# HGD_Sensor_v0_2_-20200901.net
KiCad netlist of a schematic drawn in Altium Designer
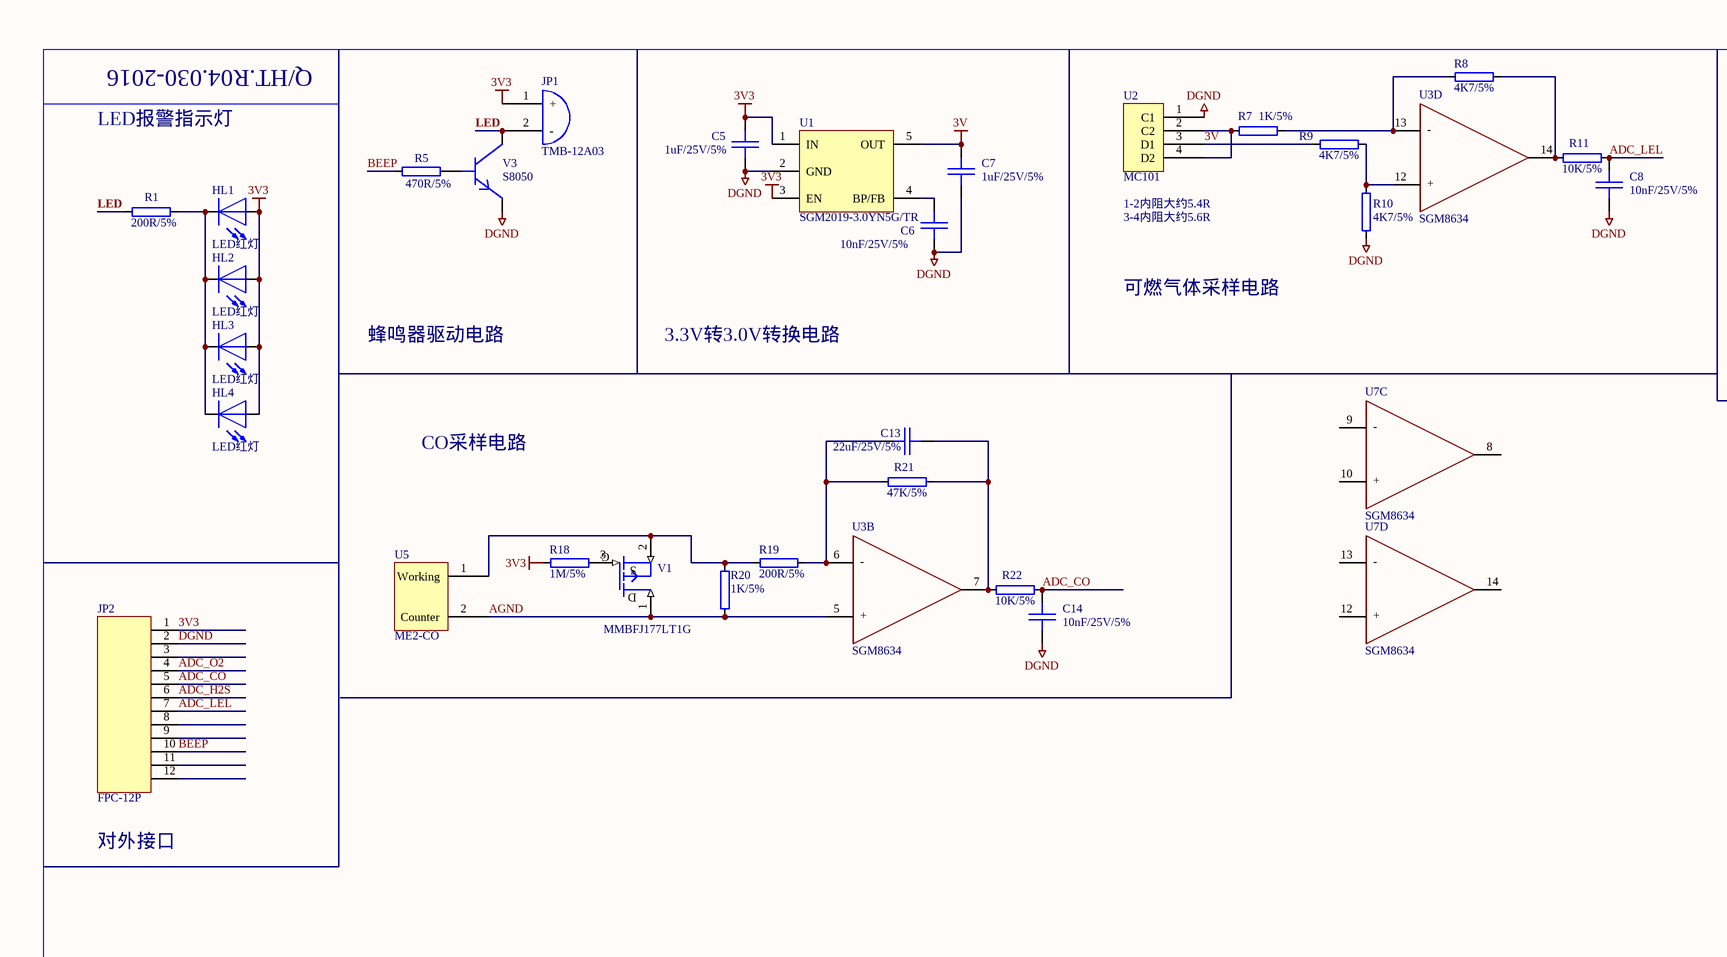
[diagram p0: HGD_Sensor(v0.2)-20200901.SchDoc, top left]
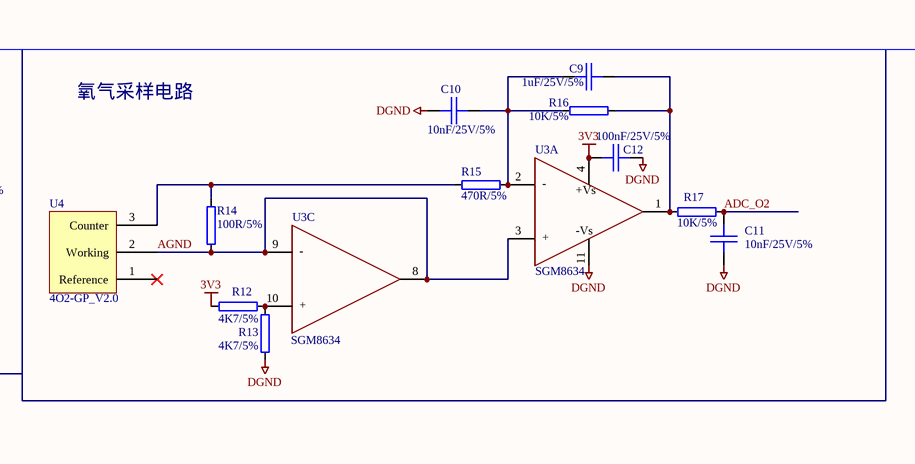
[diagram p1: HGD_Sensor(v0.2)-20200901.SchDoc, top right]
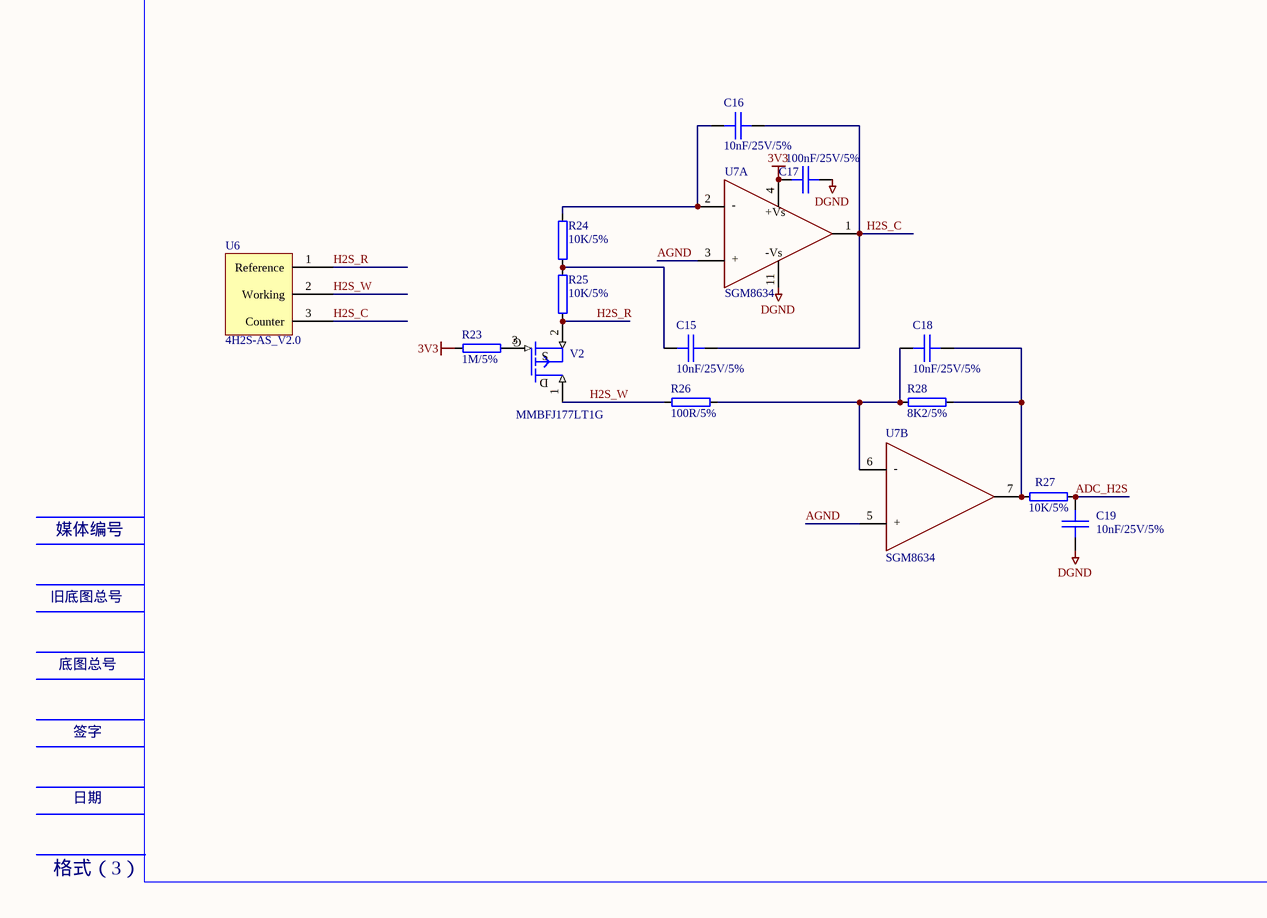
[diagram p2: HGD_Sensor(v0.2)-20200901.SchDoc, bottom left]
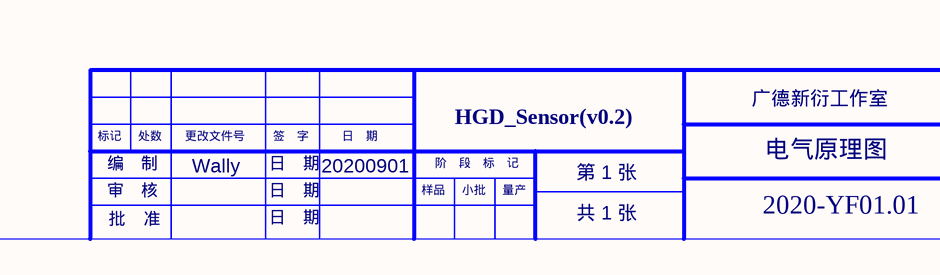
[diagram p3: HGD_Sensor(v0.2)-20200901.SchDoc, bottom right]

(export (version "E")
  (design (tool "Eeschema 10.0.6"))
  (components
    (comp (ref "C5")
      (value "1uF/25V/5%")
      (footprint "0805")
      (description "电容")
      (libsource (lib "*") (part "CAP"))
    )
    (comp (ref "C6")
      (value "10nF/25V/5%")
      (footprint "C0603")
      (description "电容")
      (libsource (lib "*") (part "CAP"))
    )
    (comp (ref "C7")
      (value "1uF/25V/5%")
      (footprint "0805")
      (description "电容")
      (libsource (lib "*") (part "CAP"))
    )
    (comp (ref "C8")
      (value "10nF/25V/5%")
      (footprint "C0603")
      (description "电容")
      (libsource (lib "*") (part "CAP"))
    )
    (comp (ref "C9")
      (value "1uF/25V/5%")
      (footprint "0805")
      (description "电容")
      (libsource (lib "*") (part "CAP"))
    )
    (comp (ref "C10")
      (value "10nF/25V/5%")
      (footprint "C0603")
      (description "电容")
      (libsource (lib "*") (part "CAP"))
    )
    (comp (ref "C11")
      (value "10nF/25V/5%")
      (footprint "C0603")
      (description "电容")
      (libsource (lib "*") (part "CAP"))
    )
    (comp (ref "C12")
      (value "100nF/25V/5%")
      (footprint "C0603")
      (description "电容")
      (libsource (lib "*") (part "CAP"))
    )
    (comp (ref "C13")
      (value "22uF/25V/5%")
      (footprint "0805")
      (description "电容")
      (libsource (lib "*") (part "CAP"))
    )
    (comp (ref "C14")
      (value "10nF/25V/5%")
      (footprint "C0603")
      (description "电容")
      (libsource (lib "*") (part "CAP"))
    )
    (comp (ref "C15")
      (value "10nF/25V/5%")
      (footprint "C0603")
      (description "电容")
      (libsource (lib "*") (part "CAP"))
    )
    (comp (ref "C16")
      (value "10nF/25V/5%")
      (footprint "C0603")
      (description "电容")
      (libsource (lib "*") (part "CAP"))
    )
    (comp (ref "C17")
      (value "100nF/25V/5%")
      (footprint "C0603")
      (description "电容")
      (libsource (lib "*") (part "CAP"))
    )
    (comp (ref "C18")
      (value "10nF/25V/5%")
      (footprint "C0603")
      (description "电容")
      (libsource (lib "*") (part "CAP"))
    )
    (comp (ref "C19")
      (value "10nF/25V/5%")
      (footprint "C0603")
      (description "电容")
      (libsource (lib "*") (part "CAP"))
    )
    (comp (ref "HL1")
      (value "LED红灯")
      (footprint "LED-3MM")
      (description "发光二极管")
      (libsource (lib "wypPCB_Lib") (part "发光二极管"))
    )
    (comp (ref "HL2")
      (value "LED红灯")
      (footprint "LED-3MM")
      (description "发光二极管")
      (libsource (lib "wypPCB_Lib") (part "发光二极管"))
    )
    (comp (ref "HL3")
      (value "LED红灯")
      (footprint "LED-3MM")
      (description "发光二极管")
      (libsource (lib "wypPCB_Lib") (part "发光二极管"))
    )
    (comp (ref "HL4")
      (value "LED红灯")
      (footprint "LED-3MM")
      (description "发光二极管")
      (libsource (lib "wypPCB_Lib") (part "发光二极管"))
    )
    (comp (ref "JP1")
      (value "TMB-12A03")
      (footprint "TMB-12A03")
      (description "TMB-12A03：3.3V有源蜂鸣器")
      (libsource (lib "wypPCB_Lib") (part "TMB-12A03"))
    )
    (comp (ref "JP2")
      (value "FPC-12P")
      (footprint "FPC-1.0MM-12P-W")
      (libsource (lib "wypPCB_Lib") (part "FPC-12P"))
    )
    (comp (ref "R1")
      (value "200R/5%")
      (footprint "R0603")
      (description "电阻")
      (libsource (lib "*") (part "RES2"))
    )
    (comp (ref "R5")
      (value "470R/5%")
      (footprint "R0603")
      (description "电阻")
      (libsource (lib "*") (part "RES2"))
    )
    (comp (ref "R7")
      (value "1K/5%")
      (footprint "R0603")
      (description "电阻")
      (libsource (lib "*") (part "RES2"))
    )
    (comp (ref "R8")
      (value "4K7/5%")
      (footprint "R0603")
      (description "电阻")
      (libsource (lib "*") (part "RES2"))
    )
    (comp (ref "R9")
      (value "4K7/5%")
      (footprint "R0603")
      (description "电阻")
      (libsource (lib "*") (part "RES2"))
    )
    (comp (ref "R10")
      (value "4K7/5%")
      (footprint "R0603")
      (description "电阻")
      (libsource (lib "*") (part "RES2"))
    )
    (comp (ref "R11")
      (value "10K/5%")
      (footprint "R0603")
      (description "电阻")
      (libsource (lib "*") (part "RES2"))
    )
    (comp (ref "R12")
      (value "4K7/5%")
      (footprint "R0603")
      (description "电阻")
      (libsource (lib "*") (part "RES2"))
    )
    (comp (ref "R13")
      (value "4K7/5%")
      (footprint "R0603")
      (description "电阻")
      (libsource (lib "*") (part "RES2"))
    )
    (comp (ref "R14")
      (value "100R/5%")
      (footprint "R0603")
      (description "电阻")
      (libsource (lib "*") (part "RES2"))
    )
    (comp (ref "R15")
      (value "470R/5%")
      (footprint "R0603")
      (description "电阻")
      (libsource (lib "*") (part "RES2"))
    )
    (comp (ref "R16")
      (value "10K/5%")
      (footprint "R0603")
      (description "电阻")
      (libsource (lib "*") (part "RES2"))
    )
    (comp (ref "R17")
      (value "10K/5%")
      (footprint "R0603")
      (description "电阻")
      (libsource (lib "*") (part "RES2"))
    )
    (comp (ref "R18")
      (value "1M/5%")
      (footprint "R0603")
      (description "电阻")
      (libsource (lib "*") (part "RES2"))
    )
    (comp (ref "R19")
      (value "200R/5%")
      (footprint "R0603")
      (description "电阻")
      (libsource (lib "*") (part "RES2"))
    )
    (comp (ref "R20")
      (value "1K/5%")
      (footprint "R0603")
      (description "电阻")
      (libsource (lib "*") (part "RES2"))
    )
    (comp (ref "R21")
      (value "47K/5%")
      (footprint "R0603")
      (description "电阻")
      (libsource (lib "*") (part "RES2"))
    )
    (comp (ref "R22")
      (value "10K/5%")
      (footprint "R0603")
      (description "电阻")
      (libsource (lib "*") (part "RES2"))
    )
    (comp (ref "R23")
      (value "1M/5%")
      (footprint "R0603")
      (description "电阻")
      (libsource (lib "*") (part "RES2"))
    )
    (comp (ref "R24")
      (value "10K/5%")
      (footprint "R0603")
      (description "电阻")
      (libsource (lib "*") (part "RES2"))
    )
    (comp (ref "R25")
      (value "10K/5%")
      (footprint "R0603")
      (description "电阻")
      (libsource (lib "*") (part "RES2"))
    )
    (comp (ref "R26")
      (value "100R/5%")
      (footprint "R0603")
      (description "电阻")
      (libsource (lib "*") (part "RES2"))
    )
    (comp (ref "R27")
      (value "10K/5%")
      (footprint "R0603")
      (description "电阻")
      (libsource (lib "*") (part "RES2"))
    )
    (comp (ref "R28")
      (value "8K2/5%")
      (footprint "R0603")
      (description "电阻")
      (libsource (lib "*") (part "RES2"))
    )
    (comp (ref "U1")
      (value "SGM2019-3.0YN5G/TR")
      (footprint "SGM2019_SOT23-5_95P280X125-5N")
      (description "SGM2019：Low Power, Low Dropout, RF Linear Regulators")
      (libsource (lib "wypPCB_Lib") (part "SGM2019"))
    )
    (comp (ref "U2")
      (value "MC101")
      (footprint "MC101")
      (description "MC101：可燃气体传感器")
      (libsource (lib "wypPCB_Lib") (part "MC101"))
    )
    (comp (ref "U3")
      (value "SGM8634")
      (footprint "SGM8634_TSSOP14_65P640X120-14N")
      (description "SGM8634：470μA, 6MHz, Rail-to-Rail I/O, CMOS Operational Amplifier")
      (libsource (lib "wypPCB_Lib") (part "SGM8634"))
    )
    (comp (ref "U4")
      (value "4O2-GP_V2.0")
      (footprint "4O2-GP_V2.0-1.5K-3.2*2.5*5.8")
      (description "4O2-GP_V2.0：O2传感器")
      (libsource (lib "wypPCB_Lib") (part "4O2-GP_V2.0"))
    )
    (comp (ref "U5")
      (value "ME2-CO")
      (footprint "ME2-CO_1.5K-3.2*2.5*5.8")
      (description "ME2-CO：CO传感器")
      (libsource (lib "wypPCB_Lib") (part "ME2-CO"))
    )
    (comp (ref "U6")
      (value "4H2S-AS_V2.0")
      (footprint "4H2S-AS_V2.0-1.5K-3.0*2.5*5.8")
      (description "4H2S-AS_V2.0：H2S传感器")
      (libsource (lib "wypPCB_Lib") (part "4H2S-AS_V2.0"))
    )
    (comp (ref "U7")
      (value "SGM8634")
      (footprint "SGM8634_TSSOP14_65P640X120-14N")
      (description "SGM8634：470μA, 6MHz, Rail-to-Rail I/O, CMOS Operational Amplifier")
      (libsource (lib "wypPCB_Lib") (part "SGM8634"))
    )
    (comp (ref "V1")
      (value "MMBFJ177LT1G")
      (footprint "MMBFJ177LT1G_SOT-23")
      (description "MMBFJ177LT1G：P-JFET?Chopper")
      (libsource (lib "wypPCB_Lib") (part "MMBFJ177LT1G"))
    )
    (comp (ref "V2")
      (value "MMBFJ177LT1G")
      (footprint "MMBFJ177LT1G_SOT-23")
      (description "MMBFJ177LT1G：P-JFET?Chopper")
      (libsource (lib "wypPCB_Lib") (part "MMBFJ177LT1G"))
    )
    (comp (ref "V3")
      (value "S8050")
      (footprint "SOT-23")
      (description "NPN三极管")
      (libsource (lib "ESLIB(v1.1)-AD9-20150731") (part "NPN"))
    )
  )
  (nets
    (net (code "1") (name "/ADC_CO") (class "Default")
      (node (ref "C14") (pin "1") (pintype "passive"))
      (node (ref "JP2") (pin "5") (pintype "passive"))
      (node (ref "R22") (pin "1") (pintype "passive"))
    )
    (net (code "2") (name "/ADC_H2S") (class "Default")
      (node (ref "C19") (pin "1") (pintype "passive"))
      (node (ref "JP2") (pin "6") (pintype "passive"))
      (node (ref "R27") (pin "2") (pintype "passive"))
    )
    (net (code "3") (name "/ADC_LEL") (class "Default")
      (node (ref "C8") (pin "1") (pintype "passive"))
      (node (ref "JP2") (pin "7") (pintype "passive"))
      (node (ref "R11") (pin "1") (pintype "passive"))
    )
    (net (code "4") (name "/ADC_O2") (class "Default")
      (node (ref "C11") (pin "1") (pintype "passive"))
      (node (ref "JP2") (pin "4") (pintype "passive"))
      (node (ref "R17") (pin "1") (pintype "passive"))
    )
    (net (code "5") (name "/AGND") (class "Default")
      (node (ref "R14") (pin "1") (pintype "passive"))
      (node (ref "R20") (pin "2") (pintype "passive"))
      (node (ref "U3") (pin "3") (pinfunction "+_3") (pintype "passive"))
      (node (ref "U3") (pin "5") (pinfunction "+_5") (pintype "passive"))
      (node (ref "U3") (pin "8") (pintype "passive"))
      (node (ref "U3") (pin "9") (pinfunction "-_9") (pintype "passive"))
      (node (ref "U4") (pin "2") (pinfunction "Working_2") (pintype "passive"))
      (node (ref "U5") (pin "2") (pinfunction "Counter_2") (pintype "passive"))
      (node (ref "U7") (pin "3") (pinfunction "+_3") (pintype "passive"))
      (node (ref "U7") (pin "5") (pinfunction "+_5") (pintype "passive"))
      (node (ref "V1") (pin "1") (pinfunction "D_1") (pintype "input"))
    )
    (net (code "6") (name "/BEEP") (class "Default")
      (node (ref "JP2") (pin "10") (pintype "passive"))
      (node (ref "R5") (pin "1") (pintype "passive"))
    )
    (net (code "7") (name "/H2S_C") (class "Default")
      (node (ref "C15") (pin "1") (pintype "passive"))
      (node (ref "C16") (pin "2") (pintype "passive"))
      (node (ref "U6") (pin "3") (pinfunction "Counter_3") (pintype "passive"))
      (node (ref "U7") (pin "1") (pintype "passive"))
    )
    (net (code "8") (name "/H2S_R") (class "Default")
      (node (ref "R25") (pin "2") (pintype "passive"))
      (node (ref "U6") (pin "1") (pinfunction "Reference_1") (pintype "passive"))
      (node (ref "V2") (pin "2") (pinfunction "S_2") (pintype "input"))
    )
    (net (code "9") (name "/H2S_W") (class "Default")
      (node (ref "R26") (pin "1") (pintype "passive"))
      (node (ref "U6") (pin "2") (pinfunction "Working_2") (pintype "passive"))
      (node (ref "V2") (pin "1") (pinfunction "D_1") (pintype "input"))
    )
    (net (code "10") (name "/LED") (class "Default")
      (node (ref "JP1") (pin "2") (pinfunction "-_2") (pintype "passive"))
      (node (ref "R1") (pin "2") (pintype "passive"))
      (node (ref "V3") (pin "C") (pintype "passive"))
    )
    (net (code "11") (name "3V") (class "Default")
      (node (ref "C7") (pin "1") (pintype "passive"))
      (node (ref "R9") (pin "2") (pintype "passive"))
      (node (ref "U1") (pin "5") (pinfunction "OUT_5") (pintype "passive"))
      (node (ref "U2") (pin "3") (pinfunction "D1_3") (pintype "passive"))
    )
    (net (code "12") (name "3V3") (class "Default")
      (node (ref "C12") (pin "2") (pintype "passive"))
      (node (ref "C17") (pin "2") (pintype "passive"))
      (node (ref "C5") (pin "1") (pintype "passive"))
      (node (ref "HL1") (pin "A") (pintype "passive"))
      (node (ref "HL2") (pin "A") (pintype "passive"))
      (node (ref "HL3") (pin "A") (pintype "passive"))
      (node (ref "HL4") (pin "A") (pintype "passive"))
      (node (ref "JP1") (pin "1") (pinfunction "+_1") (pintype "passive"))
      (node (ref "JP2") (pin "1") (pintype "passive"))
      (node (ref "R12") (pin "2") (pintype "passive"))
      (node (ref "R18") (pin "2") (pintype "passive"))
      (node (ref "R23") (pin "2") (pintype "passive"))
      (node (ref "U1") (pin "1") (pinfunction "IN_1") (pintype "passive"))
      (node (ref "U1") (pin "3") (pinfunction "EN_3") (pintype "passive"))
      (node (ref "U3") (pin "4") (pinfunction "+Vs_4") (pintype "passive"))
      (node (ref "U7") (pin "4") (pinfunction "+Vs_4") (pintype "passive"))
    )
    (net (code "13") (name "DGND") (class "Default")
      (node (ref "C10") (pin "2") (pintype "passive"))
      (node (ref "C11") (pin "2") (pintype "passive"))
      (node (ref "C12") (pin "1") (pintype "passive"))
      (node (ref "C14") (pin "2") (pintype "passive"))
      (node (ref "C17") (pin "1") (pintype "passive"))
      (node (ref "C19") (pin "2") (pintype "passive"))
      (node (ref "C5") (pin "2") (pintype "passive"))
      (node (ref "C6") (pin "2") (pintype "passive"))
      (node (ref "C7") (pin "2") (pintype "passive"))
      (node (ref "C8") (pin "2") (pintype "passive"))
      (node (ref "JP2") (pin "2") (pintype "passive"))
      (node (ref "R10") (pin "2") (pintype "passive"))
      (node (ref "R13") (pin "2") (pintype "passive"))
      (node (ref "U1") (pin "2") (pinfunction "GND_2") (pintype "passive"))
      (node (ref "U2") (pin "1") (pinfunction "C1_1") (pintype "passive"))
      (node (ref "U3") (pin "11") (pinfunction "-Vs_11") (pintype "passive"))
      (node (ref "U7") (pin "11") (pinfunction "-Vs_11") (pintype "passive"))
      (node (ref "V3") (pin "E") (pintype "passive"))
    )
    (net (code "14") (name "Net-(C9-Pad2)") (class "Default")
      (node (ref "C9") (pin "2") (pintype "passive"))
      (node (ref "R16") (pin "1") (pintype "passive"))
      (node (ref "R17") (pin "2") (pintype "passive"))
      (node (ref "U3") (pin "1") (pintype "passive"))
    )
    (net (code "15") (name "Net-(C13-Pad2)") (class "Default")
      (node (ref "C13") (pin "2") (pintype "passive"))
      (node (ref "R21") (pin "2") (pintype "passive"))
      (node (ref "R22") (pin "2") (pintype "passive"))
      (node (ref "U3") (pin "7") (pintype "passive"))
    )
    (net (code "16") (name "Net-(C15-Pad2)") (class "Default")
      (node (ref "C15") (pin "2") (pintype "passive"))
      (node (ref "R24") (pin "2") (pintype "passive"))
      (node (ref "R25") (pin "1") (pintype "passive"))
    )
    (net (code "17") (name "Net-(C18-Pad1)") (class "Default")
      (node (ref "C18") (pin "1") (pintype "passive"))
      (node (ref "R27") (pin "1") (pintype "passive"))
      (node (ref "R28") (pin "2") (pintype "passive"))
      (node (ref "U7") (pin "7") (pintype "passive"))
    )
    (net (code "18") (name "Net-(HL1-PadK)") (class "Default")
      (node (ref "HL1") (pin "K") (pintype "passive"))
      (node (ref "HL2") (pin "K") (pintype "passive"))
      (node (ref "HL3") (pin "K") (pintype "passive"))
      (node (ref "HL4") (pin "K") (pintype "passive"))
      (node (ref "R1") (pin "1") (pintype "passive"))
    )
    (net (code "19") (name "Net-(R5-Pad2)") (class "Default")
      (node (ref "R5") (pin "2") (pintype "passive"))
      (node (ref "V3") (pin "B") (pintype "passive"))
    )
    (net (code "20") (name "Net-(R11-Pad2)") (class "Default")
      (node (ref "R11") (pin "2") (pintype "passive"))
      (node (ref "R8") (pin "1") (pintype "passive"))
      (node (ref "U3") (pin "14") (pintype "passive"))
    )
    (net (code "21") (name "Net-(U1-BP{slash}FB)") (class "Default")
      (node (ref "C6") (pin "1") (pintype "passive"))
      (node (ref "U1") (pin "4") (pinfunction "BP/FB_4") (pintype "passive"))
    )
    (net (code "22") (name "Net-(U2-C2)") (class "Default")
      (node (ref "R7") (pin "2") (pintype "passive"))
      (node (ref "U2") (pin "2") (pinfunction "C2_2") (pintype "passive"))
      (node (ref "U2") (pin "4") (pinfunction "D2_4") (pintype "passive"))
    )
    (net (code "23") (name "Net-(U3A--)") (class "Default")
      (node (ref "C10") (pin "1") (pintype "passive"))
      (node (ref "C9") (pin "1") (pintype "passive"))
      (node (ref "R15") (pin "2") (pintype "passive"))
      (node (ref "R16") (pin "2") (pintype "passive"))
      (node (ref "U3") (pin "2") (pinfunction "-_2") (pintype "passive"))
    )
    (net (code "24") (name "Net-(U3B--)") (class "Default")
      (node (ref "C13") (pin "1") (pintype "passive"))
      (node (ref "R19") (pin "1") (pintype "passive"))
      (node (ref "R21") (pin "1") (pintype "passive"))
      (node (ref "U3") (pin "6") (pinfunction "-_6") (pintype "passive"))
    )
    (net (code "25") (name "Net-(U3C-+)") (class "Default")
      (node (ref "R12") (pin "1") (pintype "passive"))
      (node (ref "R13") (pin "1") (pintype "passive"))
      (node (ref "U3") (pin "10") (pinfunction "+_10") (pintype "passive"))
    )
    (net (code "26") (name "Net-(U3D-+)") (class "Default")
      (node (ref "R10") (pin "1") (pintype "passive"))
      (node (ref "R9") (pin "1") (pintype "passive"))
      (node (ref "U3") (pin "12") (pinfunction "+_12") (pintype "passive"))
    )
    (net (code "27") (name "Net-(U3D--)") (class "Default")
      (node (ref "R7") (pin "1") (pintype "passive"))
      (node (ref "R8") (pin "2") (pintype "passive"))
      (node (ref "U3") (pin "13") (pinfunction "-_13") (pintype "passive"))
    )
    (net (code "28") (name "Net-(U4-Counter)") (class "Default")
      (node (ref "R14") (pin "2") (pintype "passive"))
      (node (ref "R15") (pin "1") (pintype "passive"))
      (node (ref "U4") (pin "3") (pinfunction "Counter_3") (pintype "passive"))
    )
    (net (code "29") (name "Net-(U5-Working)") (class "Default")
      (node (ref "R19") (pin "2") (pintype "passive"))
      (node (ref "R20") (pin "1") (pintype "passive"))
      (node (ref "U5") (pin "1") (pinfunction "Working_1") (pintype "passive"))
      (node (ref "V1") (pin "2") (pinfunction "S_2") (pintype "input"))
    )
    (net (code "30") (name "Net-(U7A--)") (class "Default")
      (node (ref "C16") (pin "1") (pintype "passive"))
      (node (ref "R24") (pin "1") (pintype "passive"))
      (node (ref "U7") (pin "2") (pinfunction "-_2") (pintype "passive"))
    )
    (net (code "31") (name "Net-(U7B--)") (class "Default")
      (node (ref "C18") (pin "2") (pintype "passive"))
      (node (ref "R26") (pin "2") (pintype "passive"))
      (node (ref "R28") (pin "1") (pintype "passive"))
      (node (ref "U7") (pin "6") (pinfunction "-_6") (pintype "passive"))
    )
    (net (code "32") (name "Net-(V1-G)") (class "Default")
      (node (ref "R18") (pin "1") (pintype "passive"))
      (node (ref "V1") (pin "3") (pinfunction "G_3") (pintype "input"))
    )
    (net (code "33") (name "Net-(V2-G)") (class "Default")
      (node (ref "R23") (pin "1") (pintype "passive"))
      (node (ref "V2") (pin "3") (pinfunction "G_3") (pintype "input"))
    )
    (net (code "34") (name "unconnected-(JP2-Pad3)") (class "Default")
      (node (ref "JP2") (pin "3") (pintype "passive"))
    )
    (net (code "35") (name "unconnected-(JP2-Pad8)") (class "Default")
      (node (ref "JP2") (pin "8") (pintype "passive"))
    )
    (net (code "36") (name "unconnected-(JP2-Pad9)") (class "Default")
      (node (ref "JP2") (pin "9") (pintype "passive"))
    )
    (net (code "37") (name "unconnected-(JP2-Pad11)") (class "Default")
      (node (ref "JP2") (pin "11") (pintype "passive"))
    )
    (net (code "38") (name "unconnected-(JP2-Pad12)") (class "Default")
      (node (ref "JP2") (pin "12") (pintype "passive"))
    )
    (net (code "39") (name "unconnected-(U4-Reference-Pad1)") (class "Default")
      (node (ref "U4") (pin "1") (pinfunction "Reference_1") (pintype "passive+no_connect"))
    )
    (net (code "40") (name "unconnected-(U7-Pad8)") (class "Default")
      (node (ref "U7") (pin "8") (pintype "passive"))
    )
    (net (code "41") (name "unconnected-(U7-Pad14)") (class "Default")
      (node (ref "U7") (pin "14") (pintype "passive"))
    )
    (net (code "42") (name "unconnected-(U7C-+-Pad10)") (class "Default")
      (node (ref "U7") (pin "10") (pinfunction "+_10") (pintype "passive"))
    )
    (net (code "43") (name "unconnected-(U7C---Pad9)") (class "Default")
      (node (ref "U7") (pin "9") (pinfunction "-_9") (pintype "passive"))
    )
    (net (code "44") (name "unconnected-(U7D-+-Pad12)") (class "Default")
      (node (ref "U7") (pin "12") (pinfunction "+_12") (pintype "passive"))
    )
    (net (code "45") (name "unconnected-(U7D---Pad13)") (class "Default")
      (node (ref "U7") (pin "13") (pinfunction "-_13") (pintype "passive"))
    )
  )
)
